# power-board-board-testing-interface-manu.net
KiCad netlist of a schematic drawn in EAGLE
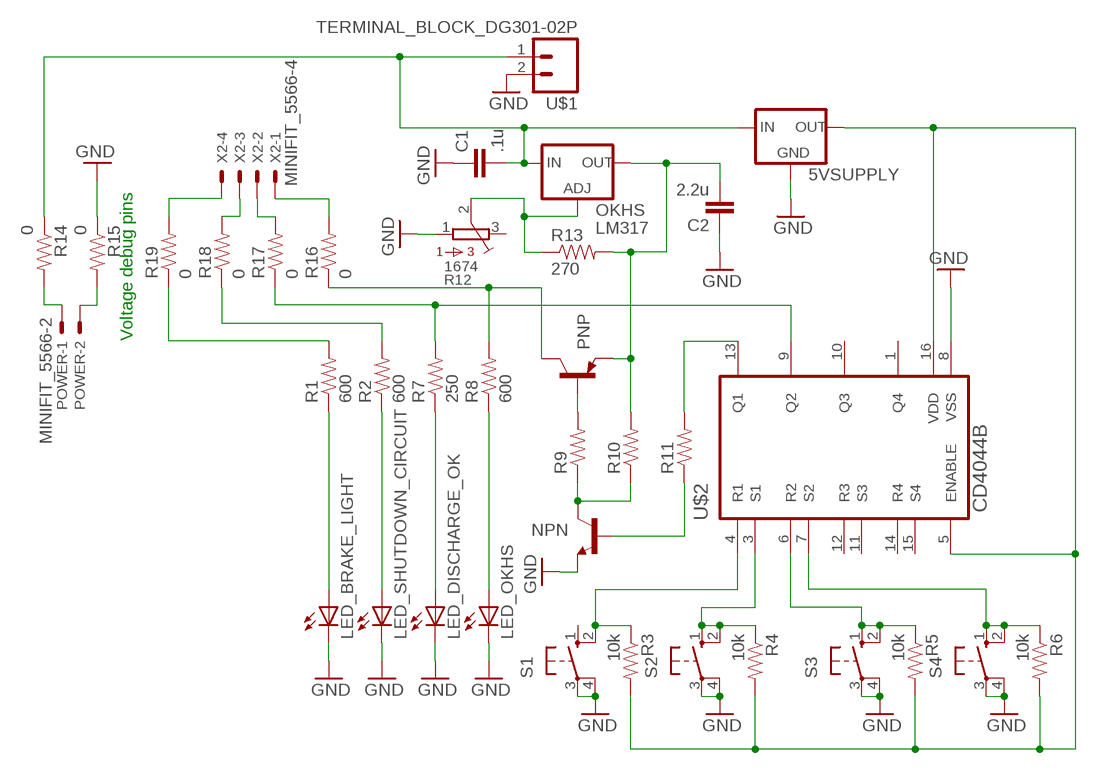
[diagram p0: schematic, sheet 1]

(export (version "E")
  (design (tool "Eeschema 10.0.6"))
  (components
    (comp (ref "5VSUPPLY")
      (value "5V_REGULATOR_L7805SWITCHING")
      (footprint "eagle-import:TO-220")
      (libsource (lib "eagle-import") (part "5V_REGULATOR_L7805SWITCHING"))
    )
    (comp (ref "C1")
      (value ".1u")
      (footprint "eagle-import:CAP-PTH-SMALLEZ")
      (libsource (lib "eagle-import") (part "CAPEZ"))
    )
    (comp (ref "C2")
      (value "2.2u")
      (footprint "eagle-import:CAP-PTH-5MM")
      (libsource (lib "eagle-import") (part "CAPPTH1"))
    )
    (comp (ref "LED_BRAKE_LIGHT")
      (value "LED-5MM")
      (footprint "eagle-import:LED-5MM")
      (libsource (lib "eagle-import") (part "LED-5MM"))
    )
    (comp (ref "LED_DISCHARGE_OK")
      (value "LED-5MM")
      (footprint "eagle-import:LED-5MM")
      (libsource (lib "eagle-import") (part "LED-5MM"))
    )
    (comp (ref "LED_OKHS")
      (value "LED-5MM")
      (footprint "eagle-import:LED-5MM")
      (libsource (lib "eagle-import") (part "LED-5MM"))
    )
    (comp (ref "LED_SHUTDOWN_CIRCUIT")
      (value "LED-5MM")
      (footprint "eagle-import:LED-5MM")
      (libsource (lib "eagle-import") (part "LED-5MM"))
    )
    (comp (ref "NPN")
      (value "BJT_NPNTIP120")
      (footprint "eagle-import:TO-220")
      (libsource (lib "eagle-import") (part "BJT_NPNTIP120"))
    )
    (comp (ref "OKHS")
      (value "LM317")
      (footprint "eagle-import:TO-220")
      (libsource (lib "eagle-import") (part "LM317"))
    )
    (comp (ref "PNP")
      (value "BJT_PNP")
      (footprint "eagle-import:TO-220")
      (libsource (lib "eagle-import") (part "BJT_PNP"))
    )
    (comp (ref "POWER")
      (value "MINIFIT_5566-2")
      (footprint "eagle-import:MINIFIT_5566-2")
      (libsource (lib "eagle-import") (part "MINIFIT_5566-2"))
    )
    (comp (ref "R1")
      (value "600")
      (footprint "eagle-import:AXIAL-0.3EZ")
      (libsource (lib "eagle-import") (part "RESISTOREZ"))
    )
    (comp (ref "R2")
      (value "600")
      (footprint "eagle-import:AXIAL-0.3EZ")
      (libsource (lib "eagle-import") (part "RESISTOREZ"))
    )
    (comp (ref "R3")
      (value "10k")
      (footprint "eagle-import:AXIAL-0.3EZ")
      (libsource (lib "eagle-import") (part "RESISTOREZ"))
    )
    (comp (ref "R4")
      (value "10k")
      (footprint "eagle-import:AXIAL-0.3EZ")
      (libsource (lib "eagle-import") (part "RESISTOREZ"))
    )
    (comp (ref "R5")
      (value "10k")
      (footprint "eagle-import:AXIAL-0.3EZ")
      (libsource (lib "eagle-import") (part "RESISTOREZ"))
    )
    (comp (ref "R6")
      (value "10k")
      (footprint "eagle-import:AXIAL-0.3EZ")
      (libsource (lib "eagle-import") (part "RESISTOREZ"))
    )
    (comp (ref "R7")
      (value "250")
      (footprint "eagle-import:AXIAL-0.3EZ")
      (libsource (lib "eagle-import") (part "RESISTOREZ"))
    )
    (comp (ref "R8")
      (value "600")
      (footprint "eagle-import:AXIAL-0.3EZ")
      (libsource (lib "eagle-import") (part "RESISTOREZ"))
    )
    (comp (ref "R9")
      (value "RESISTOREZ")
      (footprint "eagle-import:AXIAL-0.3EZ")
      (libsource (lib "eagle-import") (part "RESISTOREZ"))
    )
    (comp (ref "R10")
      (value "RESISTOREZ")
      (footprint "eagle-import:AXIAL-0.3EZ")
      (libsource (lib "eagle-import") (part "RESISTOREZ"))
    )
    (comp (ref "R11")
      (value "RESISTOREZ")
      (footprint "eagle-import:AXIAL-0.3EZ")
      (libsource (lib "eagle-import") (part "RESISTOREZ"))
    )
    (comp (ref "R12")
      (value "1674")
      (footprint "eagle-import:TRIMPOT_3296")
      (libsource (lib "eagle-import") (part "TRIMPOT_3296C"))
    )
    (comp (ref "R13")
      (value "270")
      (footprint "eagle-import:AXIAL-0.3EZ")
      (libsource (lib "eagle-import") (part "RESISTOREZ"))
    )
    (comp (ref "R14")
      (value "0")
      (footprint "eagle-import:AXIAL-0.3EZ")
      (libsource (lib "eagle-import") (part "RESISTOREZ"))
    )
    (comp (ref "R15")
      (value "0")
      (footprint "eagle-import:AXIAL-0.3EZ")
      (libsource (lib "eagle-import") (part "RESISTOREZ"))
    )
    (comp (ref "R16")
      (value "0")
      (footprint "eagle-import:AXIAL-0.3EZ")
      (libsource (lib "eagle-import") (part "RESISTOREZ"))
    )
    (comp (ref "R17")
      (value "0")
      (footprint "eagle-import:AXIAL-0.3EZ")
      (libsource (lib "eagle-import") (part "RESISTOREZ"))
    )
    (comp (ref "R18")
      (value "0")
      (footprint "eagle-import:AXIAL-0.3EZ")
      (libsource (lib "eagle-import") (part "RESISTOREZ"))
    )
    (comp (ref "R19")
      (value "0")
      (footprint "eagle-import:AXIAL-0.3EZ")
      (libsource (lib "eagle-import") (part "RESISTOREZ"))
    )
    (comp (ref "S1")
      (value "BTN_10-XX")
      (footprint "eagle-import:B3F-10XX")
      (fields (field (name "MPN") "B3F-1000"))
      (libsource (lib "eagle-import") (part "BTN_10-XX"))
    )
    (comp (ref "S2")
      (value "BTN_10-XX")
      (footprint "eagle-import:B3F-10XX")
      (fields (field (name "MPN") "B3F-1000"))
      (libsource (lib "eagle-import") (part "BTN_10-XX"))
    )
    (comp (ref "S3")
      (value "BTN_10-XX")
      (footprint "eagle-import:B3F-10XX")
      (fields (field (name "MPN") "B3F-1000"))
      (libsource (lib "eagle-import") (part "BTN_10-XX"))
    )
    (comp (ref "S4")
      (value "BTN_10-XX")
      (footprint "eagle-import:B3F-10XX")
      (fields (field (name "MPN") "B3F-1000"))
      (libsource (lib "eagle-import") (part "BTN_10-XX"))
    )
    (comp (ref "U$1")
      (value "TERMINAL_BLOCK_DG301-02P")
      (footprint "eagle-import:DG301-02P")
      (libsource (lib "eagle-import") (part "TERMINAL_BLOCK_DG301-02P"))
    )
    (comp (ref "U$2")
      (value "CD4044B")
      (footprint "eagle-import:DIL16")
      (libsource (lib "eagle-import") (part "CD4044B"))
    )
    (comp (ref "X2")
      (value "MINIFIT_5566-4")
      (footprint "eagle-import:MINIFIT_5566-4")
      (libsource (lib "eagle-import") (part "MINIFIT_5566-4"))
    )
  )
  (nets
    (net (code "1") (name "GND") (class "Default")
      (node (ref "5VSUPPLY") (pin "2") (pinfunction "GND_2") (pintype "input"))
      (node (ref "C1") (pin "1") (pinfunction "1_1") (pintype "passive"))
      (node (ref "C2") (pin "1") (pinfunction "1_1") (pintype "passive"))
      (node (ref "LED_BRAKE_LIGHT") (pin "K") (pinfunction "C_K") (pintype "passive"))
      (node (ref "LED_DISCHARGE_OK") (pin "K") (pinfunction "C_K") (pintype "passive"))
      (node (ref "LED_OKHS") (pin "K") (pinfunction "C_K") (pintype "passive"))
      (node (ref "LED_SHUTDOWN_CIRCUIT") (pin "K") (pinfunction "C_K") (pintype "passive"))
      (node (ref "NPN") (pin "3") (pinfunction "EMITTER_3") (pintype "passive"))
      (node (ref "R12") (pin "1") (pinfunction "1_1") (pintype "passive"))
      (node (ref "R15") (pin "P$1") (pinfunction "1_P$1") (pintype "passive"))
      (node (ref "S1") (pin "3") (pinfunction "P_3") (pintype "passive"))
      (node (ref "S1") (pin "4") (pinfunction "P1_4") (pintype "passive"))
      (node (ref "S2") (pin "3") (pinfunction "P_3") (pintype "passive"))
      (node (ref "S2") (pin "4") (pinfunction "P1_4") (pintype "passive"))
      (node (ref "S3") (pin "3") (pinfunction "P_3") (pintype "passive"))
      (node (ref "S3") (pin "4") (pinfunction "P1_4") (pintype "passive"))
      (node (ref "S4") (pin "3") (pinfunction "P_3") (pintype "passive"))
      (node (ref "S4") (pin "4") (pinfunction "P1_4") (pintype "passive"))
      (node (ref "U$1") (pin "2") (pinfunction "2_2") (pintype "passive"))
      (node (ref "U$2") (pin "8") (pinfunction "VSS_8") (pintype "output"))
    )
    (net (code "2") (name "Net-(5VSUPPLY-IN)") (class "Default")
      (node (ref "5VSUPPLY") (pin "1") (pinfunction "IN_1") (pintype "input"))
      (node (ref "C1") (pin "2") (pinfunction "2_2") (pintype "passive"))
      (node (ref "OKHS") (pin "3") (pinfunction "IN_3") (pintype "input"))
      (node (ref "R14") (pin "P$1") (pinfunction "1_P$1") (pintype "passive"))
      (node (ref "U$1") (pin "1") (pinfunction "1_1") (pintype "passive"))
    )
    (net (code "3") (name "Net-(5VSUPPLY-OUT)") (class "Default")
      (node (ref "5VSUPPLY") (pin "3") (pinfunction "OUT_3") (pintype "output"))
      (node (ref "R3") (pin "P$2") (pinfunction "2_P$2") (pintype "passive"))
      (node (ref "R4") (pin "P$2") (pinfunction "2_P$2") (pintype "passive"))
      (node (ref "R5") (pin "P$2") (pinfunction "2_P$2") (pintype "passive"))
      (node (ref "R6") (pin "P$2") (pinfunction "2_P$2") (pintype "passive"))
      (node (ref "U$2") (pin "16") (pinfunction "VDD_16") (pintype "input"))
      (node (ref "U$2") (pin "5") (pinfunction "ENABLE_5") (pintype "input"))
    )
    (net (code "4") (name "Net-(NPN-BASE)") (class "Default")
      (node (ref "NPN") (pin "1") (pinfunction "BASE_1") (pintype "passive"))
      (node (ref "R11") (pin "P$1") (pinfunction "1_P$1") (pintype "passive"))
    )
    (net (code "5") (name "Net-(NPN-COLLECTOR)") (class "Default")
      (node (ref "NPN") (pin "2") (pinfunction "COLLECTOR_2") (pintype "passive"))
      (node (ref "R10") (pin "P$1") (pinfunction "1_P$1") (pintype "passive"))
      (node (ref "R9") (pin "P$1") (pinfunction "1_P$1") (pintype "passive"))
    )
    (net (code "6") (name "Net-(OKHS-ADJ)") (class "Default")
      (node (ref "OKHS") (pin "1") (pinfunction "ADJ_1") (pintype "input"))
      (node (ref "R12") (pin "2") (pinfunction "2_2") (pintype "passive"))
      (node (ref "R13") (pin "P$1") (pinfunction "1_P$1") (pintype "passive"))
    )
    (net (code "7") (name "Net-(OKHS-OUT)") (class "Default")
      (node (ref "C2") (pin "2") (pinfunction "2_2") (pintype "passive"))
      (node (ref "OKHS") (pin "2") (pinfunction "OUT_2") (pintype "output"))
      (node (ref "PNP") (pin "3") (pinfunction "E_3") (pintype "passive"))
      (node (ref "R10") (pin "P$2") (pinfunction "2_P$2") (pintype "passive"))
      (node (ref "R13") (pin "P$2") (pinfunction "2_P$2") (pintype "passive"))
    )
    (net (code "8") (name "Net-(PNP-B)") (class "Default")
      (node (ref "PNP") (pin "1") (pinfunction "B_1") (pintype "passive"))
      (node (ref "R9") (pin "P$2") (pinfunction "2_P$2") (pintype "passive"))
    )
    (net (code "9") (name "Net-(PNP-C)") (class "Default")
      (node (ref "PNP") (pin "2") (pinfunction "C_2") (pintype "passive"))
      (node (ref "R16") (pin "P$1") (pinfunction "1_P$1") (pintype "passive"))
      (node (ref "R8") (pin "P$2") (pinfunction "2_P$2") (pintype "passive"))
    )
    (net (code "10") (name "Net-(POWERA-S)") (class "Default")
      (node (ref "POWER") (pin "1") (pinfunction "S_1") (pintype "passive"))
      (node (ref "R14") (pin "P$2") (pinfunction "2_P$2") (pintype "passive"))
    )
    (net (code "11") (name "Net-(POWERB-S)") (class "Default")
      (node (ref "POWER") (pin "2") (pinfunction "S_2") (pintype "passive"))
      (node (ref "R15") (pin "P$2") (pinfunction "2_P$2") (pintype "passive"))
    )
    (net (code "12") (name "Net-(R1-1)") (class "Default")
      (node (ref "LED_BRAKE_LIGHT") (pin "A") (pinfunction "A_A") (pintype "passive"))
      (node (ref "R1") (pin "P$1") (pinfunction "1_P$1") (pintype "passive"))
    )
    (net (code "13") (name "Net-(R1-2)") (class "Default")
      (node (ref "R1") (pin "P$2") (pinfunction "2_P$2") (pintype "passive"))
      (node (ref "R19") (pin "P$1") (pinfunction "1_P$1") (pintype "passive"))
    )
    (net (code "14") (name "Net-(R2-1)") (class "Default")
      (node (ref "LED_SHUTDOWN_CIRCUIT") (pin "A") (pinfunction "A_A") (pintype "passive"))
      (node (ref "R2") (pin "P$1") (pinfunction "1_P$1") (pintype "passive"))
    )
    (net (code "15") (name "Net-(R3-1)") (class "Default")
      (node (ref "R3") (pin "P$1") (pinfunction "1_P$1") (pintype "passive"))
      (node (ref "S1") (pin "2") (pinfunction "S1_2") (pintype "passive"))
      (node (ref "U$2") (pin "4") (pinfunction "R1_4") (pintype "input"))
    )
    (net (code "16") (name "Net-(R4-1)") (class "Default")
      (node (ref "R4") (pin "P$1") (pinfunction "1_P$1") (pintype "passive"))
      (node (ref "S2") (pin "1") (pinfunction "S_1") (pintype "passive"))
      (node (ref "S2") (pin "2") (pinfunction "S1_2") (pintype "passive"))
      (node (ref "U$2") (pin "3") (pinfunction "S1_3") (pintype "input"))
    )
    (net (code "17") (name "Net-(R5-1)") (class "Default")
      (node (ref "R5") (pin "P$1") (pinfunction "1_P$1") (pintype "passive"))
      (node (ref "S3") (pin "1") (pinfunction "S_1") (pintype "passive"))
      (node (ref "S3") (pin "2") (pinfunction "S1_2") (pintype "passive"))
      (node (ref "U$2") (pin "6") (pinfunction "R2_6") (pintype "input"))
    )
    (net (code "18") (name "Net-(R6-1)") (class "Default")
      (node (ref "R6") (pin "P$1") (pinfunction "1_P$1") (pintype "passive"))
      (node (ref "S4") (pin "1") (pinfunction "S_1") (pintype "passive"))
      (node (ref "S4") (pin "2") (pinfunction "S1_2") (pintype "passive"))
      (node (ref "U$2") (pin "7") (pinfunction "S2_7") (pintype "input"))
    )
    (net (code "19") (name "Net-(R7-1)") (class "Default")
      (node (ref "LED_DISCHARGE_OK") (pin "A") (pinfunction "A_A") (pintype "passive"))
      (node (ref "R7") (pin "P$1") (pinfunction "1_P$1") (pintype "passive"))
    )
    (net (code "20") (name "Net-(R8-1)") (class "Default")
      (node (ref "LED_OKHS") (pin "A") (pinfunction "A_A") (pintype "passive"))
      (node (ref "R8") (pin "P$1") (pinfunction "1_P$1") (pintype "passive"))
    )
    (net (code "21") (name "Net-(R11-2)") (class "Default")
      (node (ref "R11") (pin "P$2") (pinfunction "2_P$2") (pintype "passive"))
      (node (ref "U$2") (pin "13") (pinfunction "Q1_13") (pintype "output"))
    )
    (net (code "22") (name "Net-(R16-2)") (class "Default")
      (node (ref "R16") (pin "P$2") (pinfunction "2_P$2") (pintype "passive"))
      (node (ref "X2") (pin "1") (pinfunction "S_1") (pintype "passive"))
    )
    (net (code "23") (name "Net-(R17-1)") (class "Default")
      (node (ref "R17") (pin "P$1") (pinfunction "1_P$1") (pintype "passive"))
      (node (ref "R7") (pin "P$2") (pinfunction "2_P$2") (pintype "passive"))
      (node (ref "U$2") (pin "9") (pinfunction "Q2_9") (pintype "output"))
    )
    (net (code "24") (name "Net-(R17-2)") (class "Default")
      (node (ref "R17") (pin "P$2") (pinfunction "2_P$2") (pintype "passive"))
      (node (ref "X2") (pin "2") (pinfunction "S_2") (pintype "passive"))
    )
    (net (code "25") (name "Net-(R18-1)") (class "Default")
      (node (ref "R18") (pin "P$1") (pinfunction "1_P$1") (pintype "passive"))
      (node (ref "R2") (pin "P$2") (pinfunction "2_P$2") (pintype "passive"))
    )
    (net (code "26") (name "Net-(R18-2)") (class "Default")
      (node (ref "R18") (pin "P$2") (pinfunction "2_P$2") (pintype "passive"))
      (node (ref "X2") (pin "3") (pinfunction "S_3") (pintype "passive"))
    )
    (net (code "27") (name "Net-(R19-2)") (class "Default")
      (node (ref "R19") (pin "P$2") (pinfunction "2_P$2") (pintype "passive"))
      (node (ref "X2") (pin "4") (pinfunction "S_4") (pintype "passive"))
    )
    (net (code "28") (name "unconnected-(R12-Pad3)") (class "Default")
      (node (ref "R12") (pin "3") (pinfunction "3_3") (pintype "passive"))
    )
    (net (code "29") (name "unconnected-(S1-S-Pad1)") (class "Default")
      (node (ref "S1") (pin "1") (pinfunction "S_1") (pintype "passive"))
    )
    (net (code "30") (name "unconnected-(U$2-Q3-Pad10)") (class "Default")
      (node (ref "U$2") (pin "10") (pinfunction "Q3_10") (pintype "output"))
    )
    (net (code "31") (name "unconnected-(U$2-Q4-Pad1)") (class "Default")
      (node (ref "U$2") (pin "1") (pinfunction "Q4_1") (pintype "output"))
    )
    (net (code "32") (name "unconnected-(U$2-R3-Pad12)") (class "Default")
      (node (ref "U$2") (pin "12") (pinfunction "R3_12") (pintype "input"))
    )
    (net (code "33") (name "unconnected-(U$2-R4-Pad14)") (class "Default")
      (node (ref "U$2") (pin "14") (pinfunction "R4_14") (pintype "input"))
    )
    (net (code "34") (name "unconnected-(U$2-S3-Pad11)") (class "Default")
      (node (ref "U$2") (pin "11") (pinfunction "S3_11") (pintype "input"))
    )
    (net (code "35") (name "unconnected-(U$2-S4-Pad15)") (class "Default")
      (node (ref "U$2") (pin "15") (pinfunction "S4_15") (pintype "input"))
    )
  )
)
